# design.net
KiCad netlist of a schematic drawn in Altium Designer
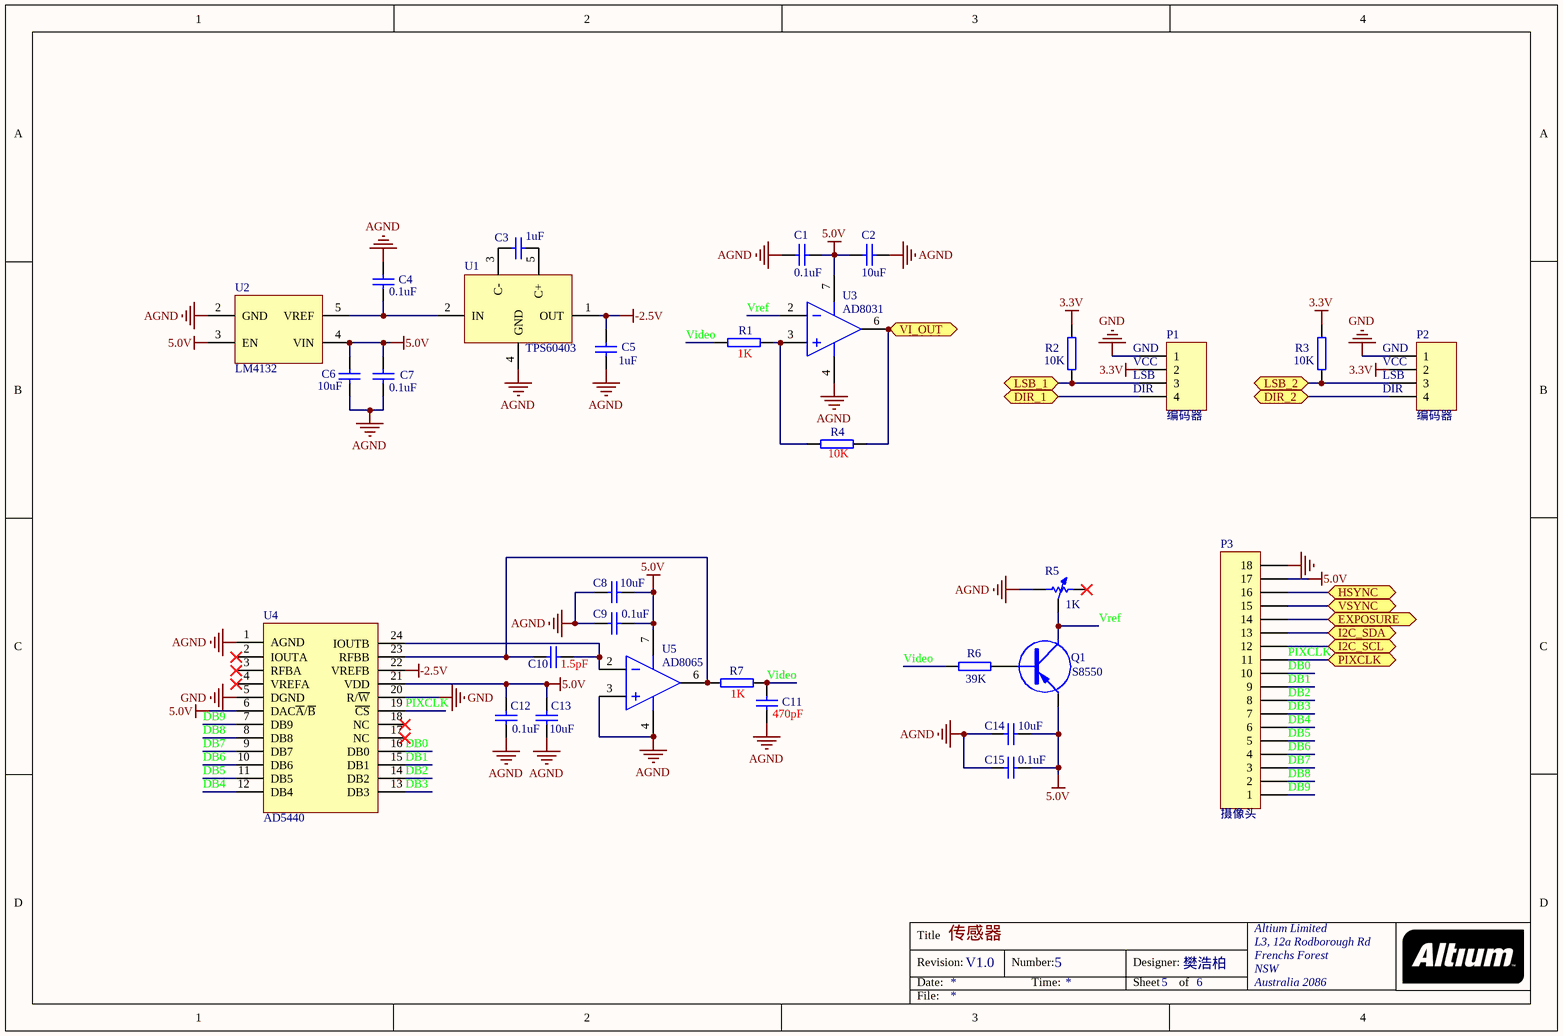
[diagram p0: 传感器.SchDoc]

(export (version "E")
  (design (tool "Eeschema 10.0.6"))
  (components
    (comp (ref "C1") (value "0.1uF") (footprint "CAP-0603") (libsource (lib "Connectors") (part "Cap")))
    (comp (ref "C2") (value "10uF") (footprint "CAP-0603") (libsource (lib "Connectors") (part "Cap")))
    (comp (ref "C3") (value "1uF") (footprint "CAP-0603") (libsource (lib "Connectors") (part "Cap")))
    (comp (ref "C4") (value "0.1uF") (footprint "CAP-0603") (libsource (lib "Connectors") (part "Cap")))
    (comp (ref "C5") (value "1uF") (footprint "CAP-0603") (libsource (lib "Connectors") (part "Cap")))
    (comp (ref "C6") (value "10uF") (footprint "CAP-0603") (libsource (lib "Connectors") (part "Cap")))
    (comp (ref "C7") (value "0.1uF") (footprint "CAP-0603") (libsource (lib "Connectors") (part "Cap")))
    (comp (ref "C8") (value "10uF") (footprint "CAP-0603") (libsource (lib "Connectors") (part "Cap")))
    (comp (ref "C9") (value "0.1uF") (footprint "CAP-0603") (libsource (lib "Connectors") (part "Cap")))
    (comp (ref "C10") (value "1.5pF") (footprint "CAP-0603") (libsource (lib "Connectors") (part "Cap")))
    (comp (ref "C11") (value "470pF") (footprint "CAP-0603") (libsource (lib "Connectors") (part "Cap")))
    (comp (ref "C12") (value "0.1uF") (footprint "CAP-0603") (libsource (lib "Connectors") (part "Cap")))
    (comp (ref "C13") (value "10uF") (footprint "CAP-0603") (libsource (lib "Connectors") (part "Cap")))
    (comp (ref "C14") (value "10uF") (footprint "CAP-0603") (libsource (lib "Connectors") (part "Cap")))
    (comp (ref "C15") (value "0.1uF") (footprint "CAP-0603") (libsource (lib "Connectors") (part "Cap")))
    (comp (ref "P1")
      (value "编码器")
      (footprint "Pin-Header-2.54-Single-4")
      (libsource (lib "Connectors-Header") (part "CON-4X1"))
    )
    (comp (ref "P2")
      (value "编码器")
      (footprint "Pin-Header-2.54-Single-4")
      (libsource (lib "Connectors-Header") (part "CON-4X1"))
    )
    (comp (ref "P3")
      (value "摄像头")
      (footprint "Header-FPC-ZIF-SMD-Vertical Single-0.5-18")
      (libsource (lib "Connectors-Header") (part "CON-18X1"))
    )
    (comp (ref "Q1") (value "S8550") (footprint "SOT-23-3") (libsource (lib "Devices") (part "PNP")))
    (comp (ref "R1") (value "1K") (footprint "RES-0603") (libsource (lib "Connectors") (part "Res")))
    (comp (ref "R2") (value "10K") (footprint "RES-0603") (libsource (lib "Connectors") (part "Res")))
    (comp (ref "R3") (value "10K") (footprint "RES-0603") (libsource (lib "Connectors") (part "Res")))
    (comp (ref "R4") (value "10K") (footprint "RES-0603") (libsource (lib "Connectors") (part "Res")))
    (comp (ref "R5") (value "1K") (footprint "RES-Adj_PVZ3") (libsource (lib "Connectors") (part "Res-Adj")))
    (comp (ref "R6") (value "39K") (footprint "RES-0603") (libsource (lib "Connectors") (part "Res")))
    (comp (ref "R7") (value "1K") (footprint "RES-0603") (libsource (lib "Connectors") (part "Res")))
    (comp (ref "U1") (value "TPS60403") (footprint "SOT-23-5") (libsource (lib "Devices") (part "TPS60403")))
    (comp (ref "U2") (value "LM4132") (footprint "SOT-23-5") (libsource (lib "Devices") (part "LM4132")))
    (comp (ref "U3")
      (value "AD8031")
      (footprint "SOT-23-5")
      (libsource (lib "Devices") (part "Op Amp_AD8065"))
    )
    (comp (ref "U4") (value "AD5440") (footprint "TSSOP-24") (libsource (lib "Devices") (part "AD5440")))
    (comp (ref "U5")
      (value "AD8065")
      (footprint "SOT-23-5")
      (libsource (lib "Devices") (part "Op Amp_AD8065"))
    )
  )
  (nets
    (net (code "1") (name "-2.5V") (class "Default")
      (node (ref "C5") (pin "1") (pinfunction "1_1") (pintype "passive"))
      (node (ref "U1") (pin "1") (pinfunction "OUT_1") (pintype "passive"))
      (node (ref "U4") (pin "22") (pinfunction "VREFB_22") (pintype "passive"))
    )
    (net (code "2") (name "/DB0") (class "Default")
      (node (ref "P3") (pin "10") (pinfunction "10_10") (pintype "passive"))
      (node (ref "U4") (pin "16") (pinfunction "DB0_16") (pintype "passive"))
    )
    (net (code "3") (name "/DB1") (class "Default")
      (node (ref "P3") (pin "9") (pinfunction "9_9") (pintype "passive"))
      (node (ref "U4") (pin "15") (pinfunction "DB1_15") (pintype "passive"))
    )
    (net (code "4") (name "/DB2") (class "Default")
      (node (ref "P3") (pin "8") (pinfunction "8_8") (pintype "passive"))
      (node (ref "U4") (pin "14") (pinfunction "DB2_14") (pintype "passive"))
    )
    (net (code "5") (name "/DB3") (class "Default")
      (node (ref "P3") (pin "7") (pinfunction "7_7") (pintype "passive"))
      (node (ref "U4") (pin "13") (pinfunction "DB3_13") (pintype "passive"))
    )
    (net (code "6") (name "/DB4") (class "Default")
      (node (ref "P3") (pin "6") (pinfunction "6_6") (pintype "passive"))
      (node (ref "U4") (pin "12") (pinfunction "DB4_12") (pintype "passive"))
    )
    (net (code "7") (name "/DB5") (class "Default")
      (node (ref "P3") (pin "5") (pinfunction "5_5") (pintype "passive"))
      (node (ref "U4") (pin "11") (pinfunction "DB5_11") (pintype "passive"))
    )
    (net (code "8") (name "/DB6") (class "Default")
      (node (ref "P3") (pin "4") (pinfunction "4_4") (pintype "passive"))
      (node (ref "U4") (pin "10") (pinfunction "DB6_10") (pintype "passive"))
    )
    (net (code "9") (name "/DB7") (class "Default")
      (node (ref "P3") (pin "3") (pinfunction "3_3") (pintype "passive"))
      (node (ref "U4") (pin "9") (pinfunction "DB7_9") (pintype "passive"))
    )
    (net (code "10") (name "/DB8") (class "Default")
      (node (ref "P3") (pin "2") (pinfunction "2_2") (pintype "passive"))
      (node (ref "U4") (pin "8") (pinfunction "DB8_8") (pintype "passive"))
    )
    (net (code "11") (name "/DB9") (class "Default")
      (node (ref "P3") (pin "1") (pinfunction "1_1") (pintype "passive"))
      (node (ref "U4") (pin "7") (pinfunction "DB9_7") (pintype "passive"))
    )
    (net (code "12") (name "/DIR_1") (class "Default")
      (node (ref "P1") (pin "4") (pinfunction "4_4") (pintype "passive"))
    )
    (net (code "13") (name "/DIR_2") (class "Default")
      (node (ref "P2") (pin "4") (pinfunction "4_4") (pintype "passive"))
    )
    (net (code "14") (name "/EXPOSURE") (class "Default")
      (node (ref "P3") (pin "14") (pinfunction "14_14") (pintype "passive"))
    )
    (net (code "15") (name "/HSYNC") (class "Default")
      (node (ref "P3") (pin "16") (pinfunction "16_16") (pintype "passive"))
    )
    (net (code "16") (name "/I2C_SCL") (class "Default")
      (node (ref "P3") (pin "12") (pinfunction "12_12") (pintype "passive"))
    )
    (net (code "17") (name "/I2C_SDA") (class "Default")
      (node (ref "P3") (pin "13") (pinfunction "13_13") (pintype "passive"))
    )
    (net (code "18") (name "/LSB_1") (class "Default")
      (node (ref "P1") (pin "3") (pinfunction "3_3") (pintype "passive"))
      (node (ref "R2") (pin "1") (pinfunction "1_1") (pintype "passive"))
    )
    (net (code "19") (name "/LSB_2") (class "Default")
      (node (ref "P2") (pin "3") (pinfunction "3_3") (pintype "passive"))
      (node (ref "R3") (pin "1") (pinfunction "1_1") (pintype "passive"))
    )
    (net (code "20") (name "/PIXCLK") (class "Default")
      (node (ref "P3") (pin "11") (pinfunction "11_11") (pintype "passive"))
      (node (ref "U4") (pin "19") (pinfunction "~{CS}_19") (pintype "passive"))
    )
    (net (code "21") (name "/VI_OUT") (class "Default")
      (node (ref "R4") (pin "1") (pinfunction "1_1") (pintype "passive"))
      (node (ref "U3") (pin "6") (pinfunction "OUT_6") (pintype "passive"))
    )
    (net (code "22") (name "/VSYNC") (class "Default")
      (node (ref "P3") (pin "15") (pinfunction "15_15") (pintype "passive"))
    )
    (net (code "23") (name "/Video") (class "Default")
      (node (ref "C11") (pin "1") (pinfunction "1_1") (pintype "passive"))
      (node (ref "R1") (pin "2") (pinfunction "2_2") (pintype "passive"))
      (node (ref "R6") (pin "1") (pinfunction "1_1") (pintype "passive"))
      (node (ref "R7") (pin "1") (pinfunction "1_1") (pintype "passive"))
    )
    (net (code "24") (name "/Vref") (class "Default")
      (node (ref "Q1") (pin "3") (pinfunction "C_3") (pintype "passive"))
      (node (ref "R5") (pin "2") (pinfunction "2_2") (pintype "passive"))
      (node (ref "U3") (pin "2") (pinfunction "IN-_2") (pintype "passive"))
    )
    (net (code "25") (name "3.3V") (class "Default")
      (node (ref "P1") (pin "2") (pinfunction "2_2") (pintype "passive"))
      (node (ref "P2") (pin "2") (pinfunction "2_2") (pintype "passive"))
      (node (ref "R2") (pin "2") (pinfunction "2_2") (pintype "passive"))
      (node (ref "R3") (pin "2") (pinfunction "2_2") (pintype "passive"))
    )
    (net (code "26") (name "5.0V") (class "Default")
      (node (ref "C1") (pin "1") (pinfunction "1_1") (pintype "passive"))
      (node (ref "C12") (pin "2") (pinfunction "2_2") (pintype "passive"))
      (node (ref "C13") (pin "2") (pinfunction "2_2") (pintype "passive"))
      (node (ref "C14") (pin "1") (pinfunction "1_1") (pintype "passive"))
      (node (ref "C15") (pin "1") (pinfunction "1_1") (pintype "passive"))
      (node (ref "C2") (pin "1") (pinfunction "1_1") (pintype "passive"))
      (node (ref "C6") (pin "1") (pinfunction "1_1") (pintype "passive"))
      (node (ref "C7") (pin "1") (pinfunction "1_1") (pintype "passive"))
      (node (ref "C8") (pin "1") (pinfunction "1_1") (pintype "passive"))
      (node (ref "C9") (pin "1") (pinfunction "1_1") (pintype "passive"))
      (node (ref "P3") (pin "17") (pinfunction "17_17") (pintype "passive"))
      (node (ref "Q1") (pin "2") (pinfunction "E_2") (pintype "passive"))
      (node (ref "U2") (pin "3") (pinfunction "EN_3") (pintype "passive"))
      (node (ref "U2") (pin "4") (pinfunction "VIN_4") (pintype "passive"))
      (node (ref "U3") (pin "7") (pinfunction "V+_7") (pintype "power_in"))
      (node (ref "U4") (pin "21") (pinfunction "VDD_21") (pintype "passive"))
      (node (ref "U4") (pin "6") (pinfunction "DAC~{A}/~{B}_6") (pintype "passive"))
      (node (ref "U5") (pin "7") (pinfunction "V+_7") (pintype "power_in"))
    )
    (net (code "27") (name "AGND") (class "Default")
      (node (ref "C1") (pin "2") (pinfunction "2_2") (pintype "passive"))
      (node (ref "C11") (pin "2") (pinfunction "2_2") (pintype "passive"))
      (node (ref "C12") (pin "1") (pinfunction "1_1") (pintype "passive"))
      (node (ref "C13") (pin "1") (pinfunction "1_1") (pintype "passive"))
      (node (ref "C14") (pin "2") (pinfunction "2_2") (pintype "passive"))
      (node (ref "C15") (pin "2") (pinfunction "2_2") (pintype "passive"))
      (node (ref "C2") (pin "2") (pinfunction "2_2") (pintype "passive"))
      (node (ref "C4") (pin "2") (pinfunction "2_2") (pintype "passive"))
      (node (ref "C5") (pin "2") (pinfunction "2_2") (pintype "passive"))
      (node (ref "C6") (pin "2") (pinfunction "2_2") (pintype "passive"))
      (node (ref "C7") (pin "2") (pinfunction "2_2") (pintype "passive"))
      (node (ref "C8") (pin "2") (pinfunction "2_2") (pintype "passive"))
      (node (ref "C9") (pin "2") (pinfunction "2_2") (pintype "passive"))
      (node (ref "R5") (pin "1") (pinfunction "1_1") (pintype "passive"))
      (node (ref "U1") (pin "4") (pinfunction "GND_4") (pintype "passive"))
      (node (ref "U2") (pin "2") (pinfunction "GND_2") (pintype "passive"))
      (node (ref "U3") (pin "4") (pinfunction "V-_4") (pintype "power_in"))
      (node (ref "U4") (pin "1") (pinfunction "AGND_1") (pintype "passive"))
      (node (ref "U5") (pin "3") (pinfunction "IN+_3") (pintype "passive"))
      (node (ref "U5") (pin "4") (pinfunction "V-_4") (pintype "power_in"))
    )
    (net (code "28") (name "GND") (class "Default")
      (node (ref "P1") (pin "1") (pinfunction "1_1") (pintype "passive"))
      (node (ref "P2") (pin "1") (pinfunction "1_1") (pintype "passive"))
      (node (ref "P3") (pin "18") (pinfunction "18_18") (pintype "passive"))
      (node (ref "U4") (pin "20") (pinfunction "R/~{W}_20") (pintype "passive"))
      (node (ref "U4") (pin "5") (pinfunction "DGND_5") (pintype "passive"))
    )
    (net (code "29") (name "Net-(Q1-B)") (class "Default")
      (node (ref "Q1") (pin "1") (pinfunction "B_1") (pintype "passive"))
      (node (ref "R6") (pin "2") (pinfunction "2_2") (pintype "passive"))
    )
    (net (code "30") (name "Net-(U1-C+)") (class "Default")
      (node (ref "C3") (pin "1") (pinfunction "1_1") (pintype "passive"))
      (node (ref "U1") (pin "5") (pinfunction "C+_5") (pintype "passive"))
    )
    (net (code "31") (name "Net-(U1-C-)") (class "Default")
      (node (ref "C3") (pin "2") (pinfunction "2_2") (pintype "passive"))
      (node (ref "U1") (pin "3") (pinfunction "C-_3") (pintype "passive"))
    )
    (net (code "32") (name "Net-(U1-IN)") (class "Default")
      (node (ref "C4") (pin "1") (pinfunction "1_1") (pintype "passive"))
      (node (ref "U1") (pin "2") (pinfunction "IN_2") (pintype "passive"))
      (node (ref "U2") (pin "5") (pinfunction "VREF_5") (pintype "passive"))
    )
    (net (code "33") (name "Net-(U3-IN+)") (class "Default")
      (node (ref "R1") (pin "1") (pinfunction "1_1") (pintype "passive"))
      (node (ref "R4") (pin "2") (pinfunction "2_2") (pintype "passive"))
      (node (ref "U3") (pin "3") (pinfunction "IN+_3") (pintype "passive"))
    )
    (net (code "34") (name "Net-(U4-IOUTB)") (class "Default")
      (node (ref "C10") (pin "1") (pinfunction "1_1") (pintype "passive"))
      (node (ref "U4") (pin "24") (pinfunction "IOUTB_24") (pintype "passive"))
      (node (ref "U5") (pin "2") (pinfunction "IN-_2") (pintype "passive"))
    )
    (net (code "35") (name "Net-(U4-RFBB)") (class "Default")
      (node (ref "C10") (pin "2") (pinfunction "2_2") (pintype "passive"))
      (node (ref "R7") (pin "2") (pinfunction "2_2") (pintype "passive"))
      (node (ref "U4") (pin "23") (pinfunction "RFBB_23") (pintype "passive"))
      (node (ref "U5") (pin "6") (pinfunction "OUT_6") (pintype "passive"))
    )
    (net (code "36") (name "unconnected-(R5-Pad3)") (class "Default")
      (node (ref "R5") (pin "3") (pinfunction "3_3") (pintype "passive+no_connect"))
    )
    (net (code "37") (name "unconnected-(U4-IOUTA-Pad2)") (class "Default")
      (node (ref "U4") (pin "2") (pinfunction "IOUTA_2") (pintype "passive+no_connect"))
    )
    (net (code "38") (name "unconnected-(U4-NC-Pad17)") (class "Default")
      (node (ref "U4") (pin "17") (pinfunction "NC_17") (pintype "passive+no_connect"))
    )
    (net (code "39") (name "unconnected-(U4-NC-Pad18)") (class "Default")
      (node (ref "U4") (pin "18") (pinfunction "NC_18") (pintype "passive+no_connect"))
    )
    (net (code "40") (name "unconnected-(U4-RFBA-Pad3)") (class "Default")
      (node (ref "U4") (pin "3") (pinfunction "RFBA_3") (pintype "passive+no_connect"))
    )
    (net (code "41") (name "unconnected-(U4-VREFA-Pad4)") (class "Default")
      (node (ref "U4") (pin "4") (pinfunction "VREFA_4") (pintype "passive+no_connect"))
    )
  )
)
